# 13-connectors.net
KiCad netlist of a schematic drawn in Altium Designer
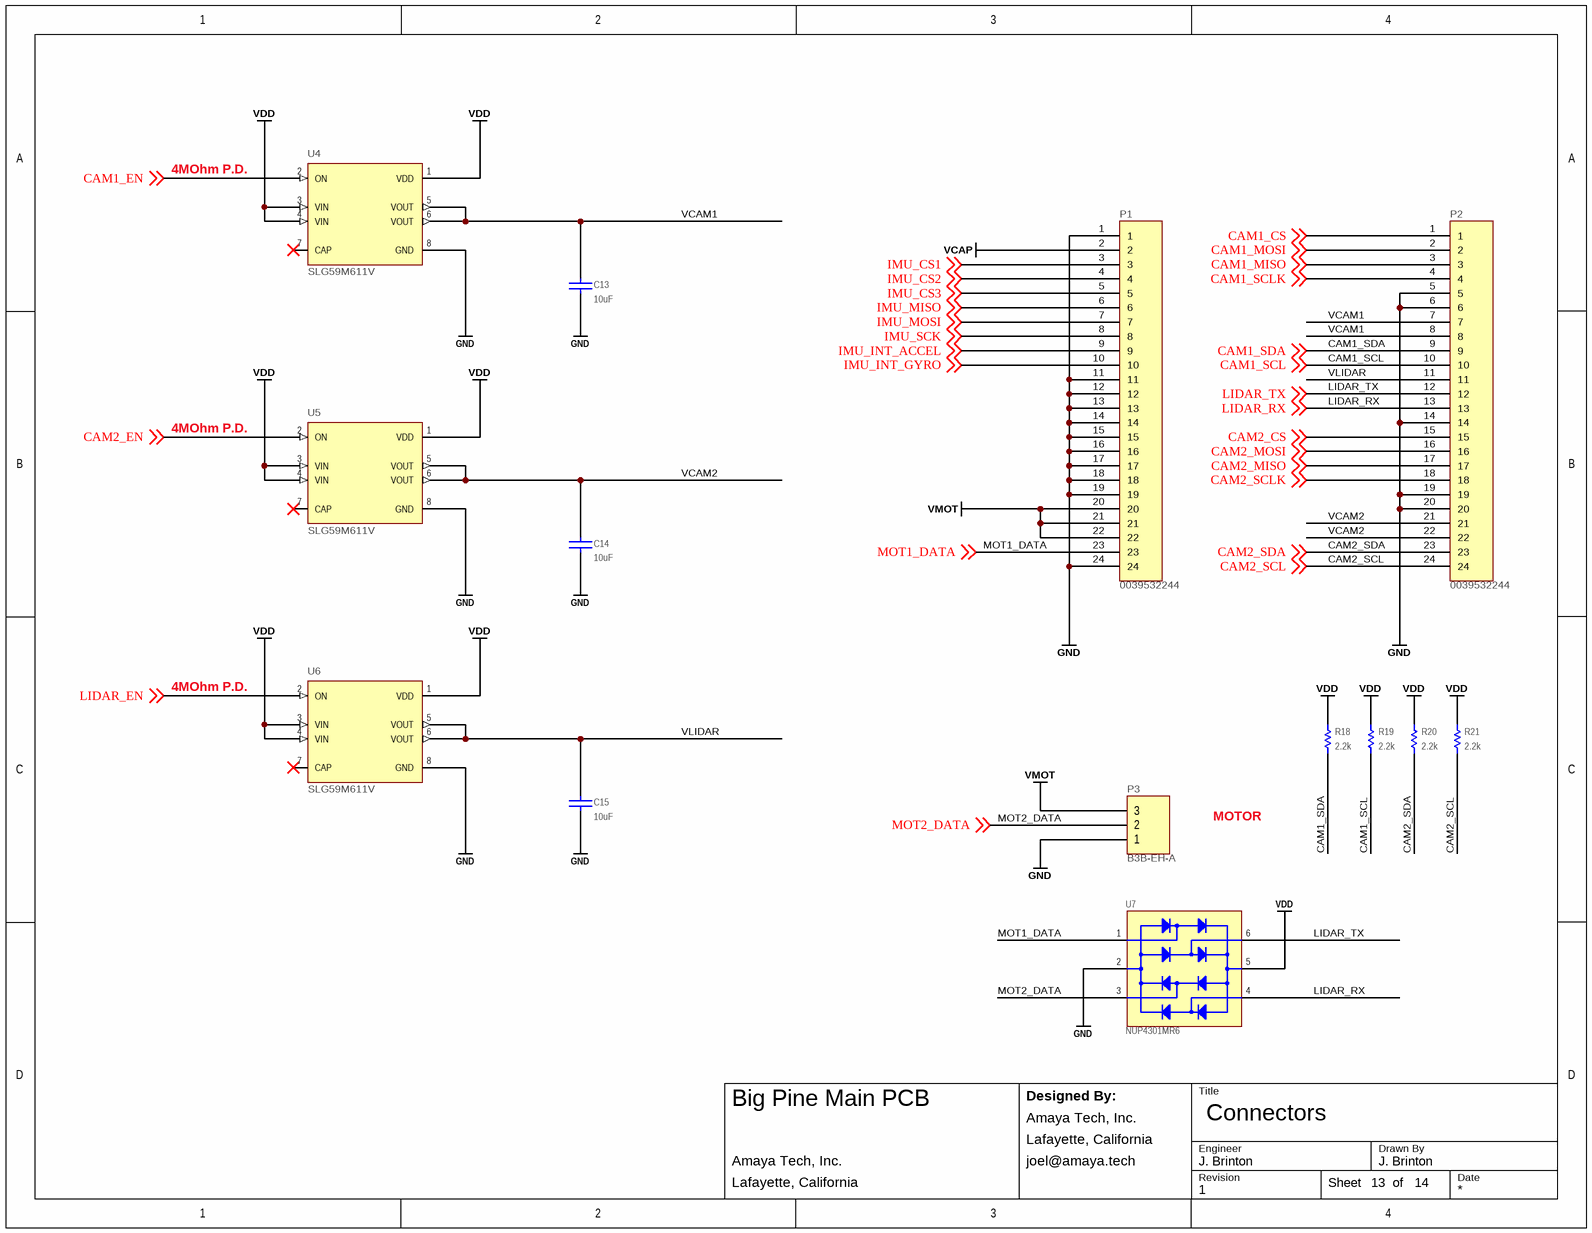
[diagram p0: 13-connectors.SchDoc]

(export (version "E")
  (design (tool "Eeschema 10.0.6"))
  (components
    (comp (ref "C13")
      (value "10uF")
      (footprint "CAPC160X80X90L20N")
      (description "Ceramic Capacitor 10uF ±20% 25V X5R 0603")
      (fields (field (name "MANUFACTURER") "Murata") (field (name "VOLTAGE") "25V"))
      (libsource (lib "generic") (part "CAP 0603"))
    )
    (comp (ref "C14")
      (value "10uF")
      (footprint "CAPC160X80X90L20N")
      (description "Ceramic Capacitor 10uF ±20% 25V X5R 0603")
      (fields (field (name "MANUFACTURER") "Murata") (field (name "VOLTAGE") "25V"))
      (libsource (lib "generic") (part "CAP 0603"))
    )
    (comp (ref "C15")
      (value "10uF")
      (footprint "CAPC160X80X90L20N")
      (description "Ceramic Capacitor 10uF ±20% 25V X5R 0603")
      (fields (field (name "MANUFACTURER") "Murata") (field (name "VOLTAGE") "25V"))
      (libsource (lib "generic") (part "CAP 0603"))
    )
    (comp (ref "P1")
      (value "0039532244")
      (footprint "0039532244")
      (description "FPC connector")
      (fields (field (name "MANUFACTURER") "Molex"))
      (libsource (lib "molex") (part "0039532244"))
    )
    (comp (ref "P2")
      (value "0039532244")
      (footprint "0039532244")
      (description "FPC connector")
      (fields (field (name "MANUFACTURER") "Molex"))
      (libsource (lib "molex") (part "0039532244"))
    )
    (comp (ref "P3")
      (value "B3B-EH-A")
      (footprint "B3B-EH-A")
      (description "2.5mm pitch crimp connector")
      (fields (field (name "MANUFACTURER") "JST"))
      (libsource (lib "Miscellaneous Connectors") (part "Header 3"))
    )
    (comp (ref "R18")
      (value "2.2k")
      (footprint "RESC2012X70N")
      (description "Thin Film Resistor 2.2k ±0.1% 0.125W 100V 0805")
      (fields (field (name "TOLERANCE") "±0.1%") (field (name "MANUFACTURER") "Panasonic"))
      (libsource (lib "generic") (part "RES"))
    )
    (comp (ref "R19")
      (value "2.2k")
      (footprint "RESC2012X70N")
      (description "Thin Film Resistor 2.2k ±0.1% 0.125W 100V 0805")
      (fields (field (name "TOLERANCE") "±0.1%") (field (name "MANUFACTURER") "Panasonic"))
      (libsource (lib "generic") (part "RES"))
    )
    (comp (ref "R20")
      (value "2.2k")
      (footprint "RESC2012X70N")
      (description "Thin Film Resistor 2.2k ±0.1% 0.125W 100V 0805")
      (fields (field (name "TOLERANCE") "±0.1%") (field (name "MANUFACTURER") "Panasonic"))
      (libsource (lib "generic") (part "RES"))
    )
    (comp (ref "R21")
      (value "2.2k")
      (footprint "RESC2012X70N")
      (description "Thin Film Resistor 2.2k ±0.1% 0.125W 100V 0805")
      (fields (field (name "TOLERANCE") "±0.1%") (field (name "MANUFACTURER") "Panasonic"))
      (libsource (lib "generic") (part "RES"))
    )
    (comp (ref "U4")
      (value "SLG59M611V")
      (footprint "DFN200X150X80-8N")
      (description "High-Side Load Switch")
      (fields (field (name "MANUFACTURER") "Silego"))
      (libsource (lib "silego") (part "SLG59M611V"))
    )
    (comp (ref "U5")
      (value "SLG59M611V")
      (footprint "DFN200X150X80-8N")
      (description "High-Side Load Switch")
      (fields (field (name "MANUFACTURER") "Silego"))
      (libsource (lib "silego") (part "SLG59M611V"))
    )
    (comp (ref "U6")
      (value "SLG59M611V")
      (footprint "DFN200X150X80-8N")
      (description "High-Side Load Switch")
      (fields (field (name "MANUFACTURER") "Silego"))
      (libsource (lib "silego") (part "SLG59M611V"))
    )
    (comp (ref "U7")
      (value "NUP4301MR6")
      (footprint "generic:SOT23-6")
      (description "4-Lane TVS Diode Array")
      (fields (field (name "MANUFACTURER") "On Semiconductor"))
      (libsource (lib "on_semi") (part "NUP4301MR6"))
    )
  )
  (nets
    (net (code "1") (name "/VCAM1") (class "Default")
      (node (ref "C13") (pin "2") (pinfunction "2_2") (pintype "passive"))
      (node (ref "P2") (pin "7") (pinfunction "7_7") (pintype "passive"))
      (node (ref "P2") (pin "8") (pinfunction "8_8") (pintype "passive"))
      (node (ref "U4") (pin "5") (pinfunction "VOUT_5") (pintype "output"))
      (node (ref "U4") (pin "6") (pinfunction "VOUT_6") (pintype "output"))
    )
    (net (code "2") (name "/VCAM2") (class "Default")
      (node (ref "C14") (pin "2") (pinfunction "2_2") (pintype "passive"))
      (node (ref "P2") (pin "21") (pinfunction "21_21") (pintype "passive"))
      (node (ref "P2") (pin "22") (pinfunction "22_22") (pintype "passive"))
      (node (ref "U5") (pin "5") (pinfunction "VOUT_5") (pintype "output"))
      (node (ref "U5") (pin "6") (pinfunction "VOUT_6") (pintype "output"))
    )
    (net (code "3") (name "/VLIDAR") (class "Default")
      (node (ref "C15") (pin "2") (pinfunction "2_2") (pintype "passive"))
      (node (ref "P2") (pin "11") (pinfunction "11_11") (pintype "passive"))
      (node (ref "U6") (pin "5") (pinfunction "VOUT_5") (pintype "output"))
      (node (ref "U6") (pin "6") (pinfunction "VOUT_6") (pintype "output"))
    )
    (net (code "4") (name "CAM1_CS") (class "Default")
      (node (ref "P2") (pin "1") (pinfunction "1_1") (pintype "passive"))
    )
    (net (code "5") (name "CAM1_EN") (class "Default")
      (node (ref "U4") (pin "2") (pinfunction "ON_2") (pintype "input"))
    )
    (net (code "6") (name "CAM1_MISO") (class "Default")
      (node (ref "P2") (pin "3") (pinfunction "3_3") (pintype "passive"))
    )
    (net (code "7") (name "CAM1_MOSI") (class "Default")
      (node (ref "P2") (pin "2") (pinfunction "2_2") (pintype "passive"))
    )
    (net (code "8") (name "CAM1_SCL") (class "Default")
      (node (ref "P2") (pin "10") (pinfunction "10_10") (pintype "passive"))
      (node (ref "R19") (pin "1") (pinfunction "1_1") (pintype "passive"))
    )
    (net (code "9") (name "CAM1_SCLK") (class "Default")
      (node (ref "P2") (pin "4") (pinfunction "4_4") (pintype "passive"))
    )
    (net (code "10") (name "CAM1_SDA") (class "Default")
      (node (ref "P2") (pin "9") (pinfunction "9_9") (pintype "passive"))
      (node (ref "R18") (pin "1") (pinfunction "1_1") (pintype "passive"))
    )
    (net (code "11") (name "CAM2_CS") (class "Default")
      (node (ref "P2") (pin "15") (pinfunction "15_15") (pintype "passive"))
    )
    (net (code "12") (name "CAM2_EN") (class "Default")
      (node (ref "U5") (pin "2") (pinfunction "ON_2") (pintype "input"))
    )
    (net (code "13") (name "CAM2_MISO") (class "Default")
      (node (ref "P2") (pin "17") (pinfunction "17_17") (pintype "passive"))
    )
    (net (code "14") (name "CAM2_MOSI") (class "Default")
      (node (ref "P2") (pin "16") (pinfunction "16_16") (pintype "passive"))
    )
    (net (code "15") (name "CAM2_SCL") (class "Default")
      (node (ref "P2") (pin "24") (pinfunction "24_24") (pintype "passive"))
      (node (ref "R21") (pin "1") (pinfunction "1_1") (pintype "passive"))
    )
    (net (code "16") (name "CAM2_SCLK") (class "Default")
      (node (ref "P2") (pin "18") (pinfunction "18_18") (pintype "passive"))
    )
    (net (code "17") (name "CAM2_SDA") (class "Default")
      (node (ref "P2") (pin "23") (pinfunction "23_23") (pintype "passive"))
      (node (ref "R20") (pin "1") (pinfunction "1_1") (pintype "passive"))
    )
    (net (code "18") (name "GND") (class "Default")
      (node (ref "C13") (pin "1") (pinfunction "1_1") (pintype "passive"))
      (node (ref "C14") (pin "1") (pinfunction "1_1") (pintype "passive"))
      (node (ref "C15") (pin "1") (pinfunction "1_1") (pintype "passive"))
      (node (ref "P1") (pin "1") (pinfunction "1_1") (pintype "passive"))
      (node (ref "P1") (pin "11") (pinfunction "11_11") (pintype "passive"))
      (node (ref "P1") (pin "12") (pinfunction "12_12") (pintype "passive"))
      (node (ref "P1") (pin "13") (pinfunction "13_13") (pintype "passive"))
      (node (ref "P1") (pin "14") (pinfunction "14_14") (pintype "passive"))
      (node (ref "P1") (pin "15") (pinfunction "15_15") (pintype "passive"))
      (node (ref "P1") (pin "16") (pinfunction "16_16") (pintype "passive"))
      (node (ref "P1") (pin "17") (pinfunction "17_17") (pintype "passive"))
      (node (ref "P1") (pin "18") (pinfunction "18_18") (pintype "passive"))
      (node (ref "P1") (pin "19") (pinfunction "19_19") (pintype "passive"))
      (node (ref "P1") (pin "24") (pinfunction "24_24") (pintype "passive"))
      (node (ref "P2") (pin "14") (pinfunction "14_14") (pintype "passive"))
      (node (ref "P2") (pin "19") (pinfunction "19_19") (pintype "passive"))
      (node (ref "P2") (pin "20") (pinfunction "20_20") (pintype "passive"))
      (node (ref "P2") (pin "5") (pinfunction "5_5") (pintype "passive"))
      (node (ref "P2") (pin "6") (pinfunction "6_6") (pintype "passive"))
      (node (ref "P3") (pin "1") (pinfunction "1_1") (pintype "passive"))
      (node (ref "U4") (pin "8") (pinfunction "GND_8") (pintype "power_in"))
      (node (ref "U5") (pin "8") (pinfunction "GND_8") (pintype "power_in"))
      (node (ref "U6") (pin "8") (pinfunction "GND_8") (pintype "power_in"))
      (node (ref "U7") (pin "2") (pinfunction "VN_2") (pintype "passive"))
    )
    (net (code "19") (name "IMU_CS1") (class "Default")
      (node (ref "P1") (pin "3") (pinfunction "3_3") (pintype "passive"))
    )
    (net (code "20") (name "IMU_CS2") (class "Default")
      (node (ref "P1") (pin "4") (pinfunction "4_4") (pintype "passive"))
    )
    (net (code "21") (name "IMU_CS3") (class "Default")
      (node (ref "P1") (pin "5") (pinfunction "5_5") (pintype "passive"))
    )
    (net (code "22") (name "IMU_INT_ACCEL") (class "Default")
      (node (ref "P1") (pin "9") (pinfunction "9_9") (pintype "passive"))
    )
    (net (code "23") (name "IMU_INT_GYRO") (class "Default")
      (node (ref "P1") (pin "10") (pinfunction "10_10") (pintype "passive"))
    )
    (net (code "24") (name "IMU_MISO") (class "Default")
      (node (ref "P1") (pin "6") (pinfunction "6_6") (pintype "passive"))
    )
    (net (code "25") (name "IMU_MOSI") (class "Default")
      (node (ref "P1") (pin "7") (pinfunction "7_7") (pintype "passive"))
    )
    (net (code "26") (name "IMU_SCK") (class "Default")
      (node (ref "P1") (pin "8") (pinfunction "8_8") (pintype "passive"))
    )
    (net (code "27") (name "LIDAR_EN") (class "Default")
      (node (ref "U6") (pin "2") (pinfunction "ON_2") (pintype "input"))
    )
    (net (code "28") (name "LIDAR_RX") (class "Default")
      (node (ref "P2") (pin "13") (pinfunction "13_13") (pintype "passive"))
      (node (ref "U7") (pin "4") (pinfunction "C_4") (pintype "passive"))
    )
    (net (code "29") (name "LIDAR_TX") (class "Default")
      (node (ref "P2") (pin "12") (pinfunction "12_12") (pintype "passive"))
      (node (ref "U7") (pin "6") (pinfunction "D_6") (pintype "passive"))
    )
    (net (code "30") (name "MOT1_DATA") (class "Default")
      (node (ref "P1") (pin "23") (pinfunction "23_23") (pintype "passive"))
      (node (ref "U7") (pin "1") (pinfunction "A_1") (pintype "passive"))
    )
    (net (code "31") (name "MOT2_DATA") (class "Default")
      (node (ref "P3") (pin "2") (pinfunction "2_2") (pintype "passive"))
      (node (ref "U7") (pin "3") (pinfunction "B_3") (pintype "passive"))
    )
    (net (code "32") (name "VCAP") (class "Default")
      (node (ref "P1") (pin "2") (pinfunction "2_2") (pintype "passive"))
    )
    (net (code "33") (name "VDD") (class "Default")
      (node (ref "R18") (pin "2") (pinfunction "2_2") (pintype "passive"))
      (node (ref "R19") (pin "2") (pinfunction "2_2") (pintype "passive"))
      (node (ref "R20") (pin "2") (pinfunction "2_2") (pintype "passive"))
      (node (ref "R21") (pin "2") (pinfunction "2_2") (pintype "passive"))
      (node (ref "U4") (pin "1") (pinfunction "VDD_1") (pintype "power_in"))
      (node (ref "U4") (pin "3") (pinfunction "VIN_3") (pintype "input"))
      (node (ref "U4") (pin "4") (pinfunction "VIN_4") (pintype "input"))
      (node (ref "U5") (pin "1") (pinfunction "VDD_1") (pintype "power_in"))
      (node (ref "U5") (pin "3") (pinfunction "VIN_3") (pintype "input"))
      (node (ref "U5") (pin "4") (pinfunction "VIN_4") (pintype "input"))
      (node (ref "U6") (pin "1") (pinfunction "VDD_1") (pintype "power_in"))
      (node (ref "U6") (pin "3") (pinfunction "VIN_3") (pintype "input"))
      (node (ref "U6") (pin "4") (pinfunction "VIN_4") (pintype "input"))
      (node (ref "U7") (pin "5") (pinfunction "VP_5") (pintype "passive"))
    )
    (net (code "34") (name "VMOT") (class "Default")
      (node (ref "P1") (pin "20") (pinfunction "20_20") (pintype "passive"))
      (node (ref "P1") (pin "21") (pinfunction "21_21") (pintype "passive"))
      (node (ref "P1") (pin "22") (pinfunction "22_22") (pintype "passive"))
      (node (ref "P3") (pin "3") (pinfunction "3_3") (pintype "passive"))
    )
    (net (code "35") (name "unconnected-(U4-CAP-Pad7)") (class "Default")
      (node (ref "U4") (pin "7") (pinfunction "CAP_7") (pintype "passive+no_connect"))
    )
    (net (code "36") (name "unconnected-(U5-CAP-Pad7)") (class "Default")
      (node (ref "U5") (pin "7") (pinfunction "CAP_7") (pintype "passive+no_connect"))
    )
    (net (code "37") (name "unconnected-(U6-CAP-Pad7)") (class "Default")
      (node (ref "U6") (pin "7") (pinfunction "CAP_7") (pintype "passive+no_connect"))
    )
  )
)
